# AC_PhSel.net
KiCad netlist of a schematic drawn in Altium Designer
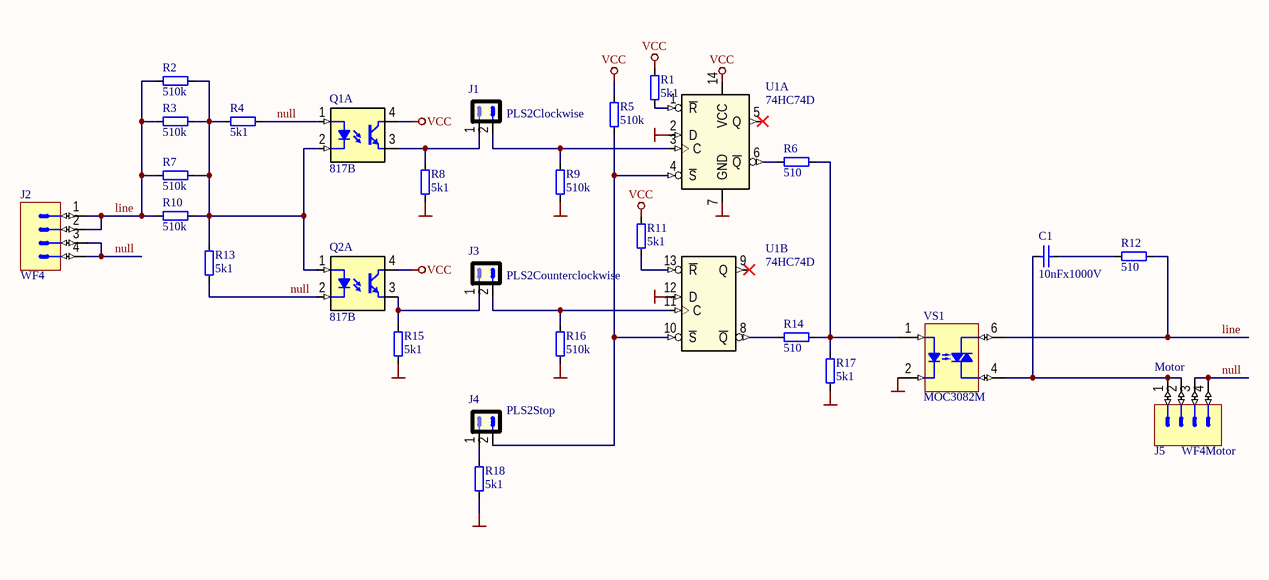
[diagram p0: AC_PhSel.SchDoc]

(export (version "E")
  (design (tool "Eeschema 10.0.6"))
  (components
    (comp (ref "C1")
      (value "10nFx1000V")
      (footprint "CAPC1206")
      (description "Чип конденсатор 0805")
      (fields (field (name "VOLTAGE") "16V") (field (name "TOLERANCE") "1%"))
      (libsource (lib "DDSintLib") (part "C1206"))
    )
    (comp (ref "J1")
      (value "PLS2Сlockwise")
      (footprint "PLS2")
      (description "PLS2")
      (libsource (lib "DDSintLib") (part "PLS2"))
    )
    (comp (ref "J2")
      (value "WF4")
      (footprint "WF4_2_54")
      (description "Вилка  WF4")
      (libsource (lib "DDSintLib") (part "WF4"))
    )
    (comp (ref "J3")
      (value "PLS2Counterclockwise")
      (footprint "PLS2")
      (description "PLS2")
      (libsource (lib "DDSintLib") (part "PLS2"))
    )
    (comp (ref "J4")
      (value "PLS2Stop")
      (footprint "PLS2")
      (description "PLS2")
      (libsource (lib "DDSintLib") (part "PLS2"))
    )
    (comp (ref "J5")
      (value "WF4Motor")
      (footprint "WF4_2_54")
      (description "Вилка  WF4")
      (fields (field (name "ALTIUM_VALUE") "Motor"))
      (libsource (lib "") (part "WF4_1"))
    )
    (comp (ref "Q1")
      (value "817B")
      (description "Optotransistor")
      (fields (field (name "VOLTAGE") "35V"))
      (libsource (lib "DDSintLib") (part "817B"))
    )
    (comp (ref "Q2")
      (value "817B")
      (description "Optotransistor")
      (fields (field (name "VOLTAGE") "35V"))
      (libsource (lib "DDSintLib") (part "817B"))
    )
    (comp (ref "R1")
      (value "5k1")
      (footprint "RESC3016X65N")
      (description "Чип резистор 1206")
      (fields (field (name "TOLERANCE") "1%"))
      (libsource (lib "DDSintLib") (part "R1206"))
    )
    (comp (ref "R2")
      (value "510k")
      (footprint "RESC3016X65N")
      (description "Чип резистор 1206")
      (fields (field (name "TOLERANCE") "1%"))
      (libsource (lib "DDSintLib") (part "R1206"))
    )
    (comp (ref "R3")
      (value "510k")
      (footprint "RESC3016X65N")
      (description "Чип резистор 1206")
      (fields (field (name "TOLERANCE") "1%"))
      (libsource (lib "DDSintLib") (part "R1206"))
    )
    (comp (ref "R4")
      (value "5k1")
      (footprint "RESC3016X65N")
      (description "Чип резистор 1206")
      (fields (field (name "TOLERANCE") "1%"))
      (libsource (lib "DDSintLib") (part "R1206"))
    )
    (comp (ref "R5")
      (value "510k")
      (footprint "RESC3016X65N")
      (description "Чип резистор 1206")
      (fields (field (name "TOLERANCE") "1%"))
      (libsource (lib "DDSintLib") (part "R1206"))
    )
    (comp (ref "R6")
      (value "510")
      (footprint "RESC3016X65N")
      (description "Чип резистор 1206")
      (fields (field (name "TOLERANCE") "1%"))
      (libsource (lib "DDSintLib") (part "R1206"))
    )
    (comp (ref "R7")
      (value "510k")
      (footprint "RESC3016X65N")
      (description "Чип резистор 1206")
      (fields (field (name "TOLERANCE") "1%"))
      (libsource (lib "DDSintLib") (part "R1206"))
    )
    (comp (ref "R8")
      (value "5k1")
      (footprint "RESC3016X65N")
      (description "Чип резистор 1206")
      (fields (field (name "TOLERANCE") "1%"))
      (libsource (lib "DDSintLib") (part "R1206"))
    )
    (comp (ref "R9")
      (value "510k")
      (footprint "RESC3016X65N")
      (description "Чип резистор 1206")
      (fields (field (name "TOLERANCE") "1%"))
      (libsource (lib "DDSintLib") (part "R1206"))
    )
    (comp (ref "R10")
      (value "510k")
      (footprint "RESC3016X65N")
      (description "Чип резистор 1206")
      (fields (field (name "TOLERANCE") "1%"))
      (libsource (lib "DDSintLib") (part "R1206"))
    )
    (comp (ref "R11")
      (value "5k1")
      (footprint "RESC3016X65N")
      (description "Чип резистор 1206")
      (fields (field (name "TOLERANCE") "1%"))
      (libsource (lib "DDSintLib") (part "R1206"))
    )
    (comp (ref "R12")
      (value "510")
      (footprint "RESC3016X65N")
      (description "Чип резистор 1206")
      (fields (field (name "TOLERANCE") "1%"))
      (libsource (lib "DDSintLib") (part "R1206"))
    )
    (comp (ref "R13")
      (value "5k1")
      (footprint "RESC3016X65N")
      (description "Чип резистор 1206")
      (fields (field (name "TOLERANCE") "1%"))
      (libsource (lib "DDSintLib") (part "R1206"))
    )
    (comp (ref "R14")
      (value "510")
      (footprint "RESC3016X65N")
      (description "Чип резистор 1206")
      (fields (field (name "TOLERANCE") "1%"))
      (libsource (lib "DDSintLib") (part "R1206"))
    )
    (comp (ref "R15")
      (value "5k1")
      (footprint "RESC3016X65N")
      (description "Чип резистор 1206")
      (fields (field (name "TOLERANCE") "1%"))
      (libsource (lib "DDSintLib") (part "R1206"))
    )
    (comp (ref "R16")
      (value "510k")
      (footprint "RESC3016X65N")
      (description "Чип резистор 1206")
      (fields (field (name "TOLERANCE") "1%"))
      (libsource (lib "DDSintLib") (part "R1206"))
    )
    (comp (ref "R17")
      (value "5k1")
      (footprint "RESC3016X65N")
      (description "Чип резистор 1206")
      (fields (field (name "TOLERANCE") "1%"))
      (libsource (lib "DDSintLib") (part "R1206"))
    )
    (comp (ref "R18")
      (value "5k1")
      (footprint "RESC3016X65N")
      (description "Чип резистор 1206")
      (fields (field (name "TOLERANCE") "1%"))
      (libsource (lib "DDSintLib") (part "R1206"))
    )
    (comp (ref "U1")
      (value "74HC74D")
      (footprint "SOIC127P600X175-14N")
      (description "Positive LDO Linear stabilizer")
      (fields (field (name "VOLTAGE") "2.. 6V"))
      (libsource (lib "DDSintLib") (part "74HC74D"))
    )
    (comp (ref "VS1")
      (value "MOC3082M")
      (footprint "DIP6-300")
      (description "Bufer CMOS in to 2xLVDS out")
      (fields (field (name "VOLTAGE") "600B"))
      (libsource (lib "DDSintLib") (part "MOC3082"))
    )
  )
  (nets
    (net (code "1") (name "/line") (class "Default")
      (node (ref "J2") (pin "1") (pinfunction "1_1") (pintype "bidirectional"))
      (node (ref "J2") (pin "2") (pinfunction "2_2") (pintype "bidirectional"))
      (node (ref "R10") (pin "1") (pinfunction "1_1") (pintype "passive"))
      (node (ref "R12") (pin "1") (pinfunction "1_1") (pintype "passive"))
      (node (ref "R2") (pin "1") (pinfunction "1_1") (pintype "passive"))
      (node (ref "R3") (pin "1") (pinfunction "1_1") (pintype "passive"))
      (node (ref "R7") (pin "1") (pinfunction "1_1") (pintype "passive"))
      (node (ref "VS1") (pin "6") (pinfunction "6_6") (pintype "bidirectional"))
    )
    (net (code "2") (name "/null") (class "Default")
      (node (ref "J2") (pin "3") (pinfunction "3_3") (pintype "bidirectional"))
      (node (ref "J2") (pin "4") (pinfunction "4_4") (pintype "bidirectional"))
      (node (ref "J5") (pin "3") (pinfunction "3_3") (pintype "bidirectional"))
      (node (ref "J5") (pin "4") (pinfunction "4_4") (pintype "bidirectional"))
      (node (ref "Q1") (pin "1") (pinfunction "A_1") (pintype "input"))
      (node (ref "Q2") (pin "2") (pinfunction "C_2") (pintype "input"))
      (node (ref "R13") (pin "1") (pinfunction "1_1") (pintype "passive"))
      (node (ref "R4") (pin "1") (pinfunction "1_1") (pintype "passive"))
    )
    (net (code "3") (name "GND") (class "Default")
      (node (ref "R15") (pin "1") (pinfunction "1_1") (pintype "passive"))
      (node (ref "R16") (pin "1") (pinfunction "1_1") (pintype "passive"))
      (node (ref "R17") (pin "1") (pinfunction "1_1") (pintype "passive"))
      (node (ref "R18") (pin "1") (pinfunction "1_1") (pintype "passive"))
      (node (ref "R8") (pin "1") (pinfunction "1_1") (pintype "passive"))
      (node (ref "R9") (pin "1") (pinfunction "1_1") (pintype "passive"))
      (node (ref "U1") (pin "12") (pinfunction "D_12") (pintype "input"))
      (node (ref "U1") (pin "2") (pinfunction "D_2") (pintype "input"))
      (node (ref "U1") (pin "7") (pinfunction "GND_7") (pintype "power_in"))
      (node (ref "VS1") (pin "2") (pinfunction "C_2") (pintype "input"))
    )
    (net (code "4") (name "Net-(C1-Pad1)") (class "Default")
      (node (ref "C1") (pin "1") (pinfunction "1_1") (pintype "passive"))
      (node (ref "J5") (pin "1") (pinfunction "1_1") (pintype "bidirectional"))
      (node (ref "J5") (pin "2") (pinfunction "2_2") (pintype "bidirectional"))
      (node (ref "VS1") (pin "4") (pinfunction "4_4") (pintype "bidirectional"))
    )
    (net (code "5") (name "Net-(C1-Pad2)") (class "Default")
      (node (ref "C1") (pin "2") (pinfunction "2_2") (pintype "passive"))
      (node (ref "R12") (pin "2") (pinfunction "2_2") (pintype "passive"))
    )
    (net (code "6") (name "Net-(J4-Pad1)") (class "Default")
      (node (ref "J4") (pin "1") (pinfunction "1_1") (pintype "bidirectional"))
      (node (ref "R18") (pin "2") (pinfunction "2_2") (pintype "passive"))
    )
    (net (code "7") (name "Net-(Q1-E)") (class "Default")
      (node (ref "J1") (pin "1") (pinfunction "1_1") (pintype "bidirectional"))
      (node (ref "Q1") (pin "3") (pinfunction "E_3") (pintype "open_emitter"))
      (node (ref "R8") (pin "2") (pinfunction "2_2") (pintype "passive"))
    )
    (net (code "8") (name "Net-(Q2-A)") (class "Default")
      (node (ref "Q1") (pin "2") (pinfunction "C_2") (pintype "input"))
      (node (ref "Q2") (pin "1") (pinfunction "A_1") (pintype "input"))
      (node (ref "R10") (pin "2") (pinfunction "2_2") (pintype "passive"))
      (node (ref "R13") (pin "2") (pinfunction "2_2") (pintype "passive"))
      (node (ref "R2") (pin "2") (pinfunction "2_2") (pintype "passive"))
      (node (ref "R3") (pin "2") (pinfunction "2_2") (pintype "passive"))
      (node (ref "R4") (pin "2") (pinfunction "2_2") (pintype "passive"))
      (node (ref "R7") (pin "2") (pinfunction "2_2") (pintype "passive"))
    )
    (net (code "9") (name "Net-(Q2-E)") (class "Default")
      (node (ref "J3") (pin "1") (pinfunction "1_1") (pintype "bidirectional"))
      (node (ref "Q2") (pin "3") (pinfunction "E_3") (pintype "open_emitter"))
      (node (ref "R15") (pin "2") (pinfunction "2_2") (pintype "passive"))
    )
    (net (code "10") (name "Net-(R6-Pad2)") (class "Default")
      (node (ref "R6") (pin "2") (pinfunction "2_2") (pintype "passive"))
      (node (ref "U1") (pin "6") (pinfunction "Q_6") (pintype "output"))
    )
    (net (code "11") (name "Net-(R14-Pad2)") (class "Default")
      (node (ref "R14") (pin "2") (pinfunction "2_2") (pintype "passive"))
      (node (ref "U1") (pin "8") (pinfunction "Q_8") (pintype "output"))
    )
    (net (code "12") (name "Net-(U1A-C)") (class "Default")
      (node (ref "J1") (pin "2") (pinfunction "2_2") (pintype "bidirectional"))
      (node (ref "R9") (pin "2") (pinfunction "2_2") (pintype "passive"))
      (node (ref "U1") (pin "3") (pinfunction "C_3") (pintype "input"))
    )
    (net (code "13") (name "Net-(U1A-R)") (class "Default")
      (node (ref "R1") (pin "1") (pinfunction "1_1") (pintype "passive"))
      (node (ref "U1") (pin "1") (pinfunction "R_1") (pintype "input"))
    )
    (net (code "14") (name "Net-(U1A-S)") (class "Default")
      (node (ref "J4") (pin "2") (pinfunction "2_2") (pintype "bidirectional"))
      (node (ref "R5") (pin "1") (pinfunction "1_1") (pintype "passive"))
      (node (ref "U1") (pin "10") (pinfunction "S_10") (pintype "input"))
      (node (ref "U1") (pin "4") (pinfunction "S_4") (pintype "input"))
    )
    (net (code "15") (name "Net-(U1B-C)") (class "Default")
      (node (ref "J3") (pin "2") (pinfunction "2_2") (pintype "bidirectional"))
      (node (ref "R16") (pin "2") (pinfunction "2_2") (pintype "passive"))
      (node (ref "U1") (pin "11") (pinfunction "C_11") (pintype "input"))
    )
    (net (code "16") (name "Net-(U1B-R)") (class "Default")
      (node (ref "R11") (pin "1") (pinfunction "1_1") (pintype "passive"))
      (node (ref "U1") (pin "13") (pinfunction "R_13") (pintype "input"))
    )
    (net (code "17") (name "Net-(VS1-A)") (class "Default")
      (node (ref "R14") (pin "1") (pinfunction "1_1") (pintype "passive"))
      (node (ref "R17") (pin "2") (pinfunction "2_2") (pintype "passive"))
      (node (ref "R6") (pin "1") (pinfunction "1_1") (pintype "passive"))
      (node (ref "VS1") (pin "1") (pinfunction "A_1") (pintype "input"))
    )
    (net (code "18") (name "VCC") (class "Default")
      (node (ref "Q1") (pin "4") (pinfunction "C_4") (pintype "open_collector"))
      (node (ref "Q2") (pin "4") (pinfunction "C_4") (pintype "open_collector"))
      (node (ref "R1") (pin "2") (pinfunction "2_2") (pintype "passive"))
      (node (ref "R11") (pin "2") (pinfunction "2_2") (pintype "passive"))
      (node (ref "R5") (pin "2") (pinfunction "2_2") (pintype "passive"))
      (node (ref "U1") (pin "14") (pinfunction "VCC_14") (pintype "power_in"))
    )
    (net (code "19") (name "unconnected-(U1A-Q-Pad5)") (class "Default")
      (node (ref "U1") (pin "5") (pinfunction "Q_5") (pintype "output+no_connect"))
    )
    (net (code "20") (name "unconnected-(U1B-Q-Pad9)") (class "Default")
      (node (ref "U1") (pin "9") (pinfunction "Q_9") (pintype "output+no_connect"))
    )
  )
)
